# 04_ETHERNET.net
KiCad netlist of a schematic drawn in Altium Designer
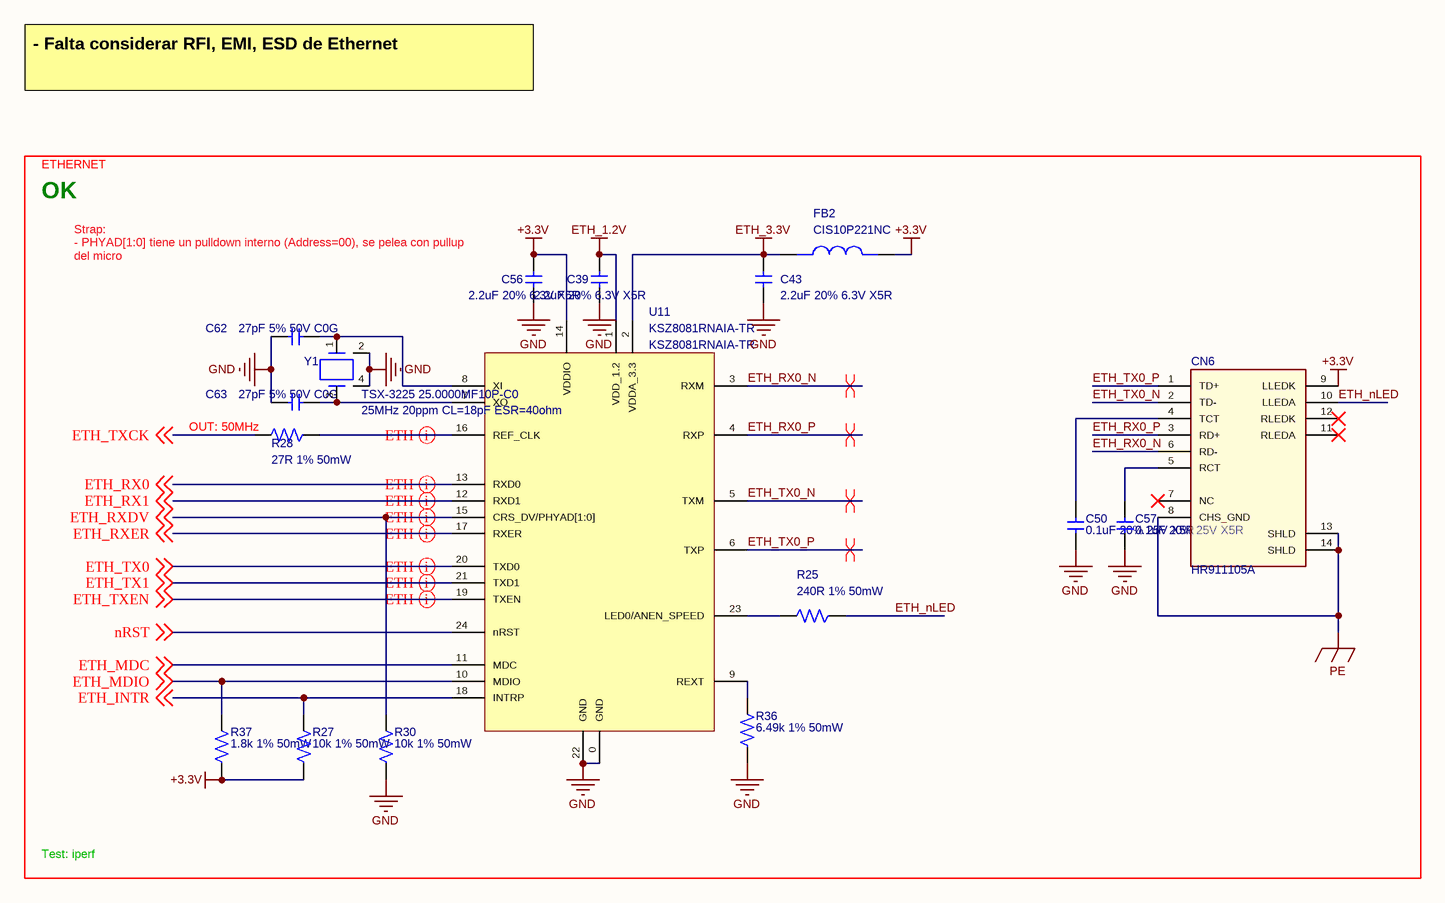
[diagram p0: 04_ETHERNET.SchDoc]

(export (version "E")
  (design (tool "Eeschema 10.0.6"))
  (components
    (comp (ref "C39")
      (value "2.2uF 20% 6.3V X5R")
      (footprint "CAPC1608X90N")
      (description "Capacitor, Ceramic")
      (fields
        (field (name "MFG") "SAMSUNG")
        (field (name "TOLERANCE") "20%")
        (field (name "FOOTPRINT CHECKED") "Assign OK, Footprint OK")
      )
      (libsource (lib "*") (part "C_Dup1"))
    )
    (comp (ref "C43")
      (value "2.2uF 20% 6.3V X5R")
      (footprint "CAPC1608X90N")
      (description "Capacitor, Ceramic")
      (fields
        (field (name "MFG") "SAMSUNG")
        (field (name "TOLERANCE") "20%")
        (field (name "FOOTPRINT CHECKED") "Assign OK, Footprint OK")
      )
      (libsource (lib "*") (part "C_Dup1"))
    )
    (comp (ref "C50")
      (value "0.1uF 20% 25V X5R")
      (footprint "CAPC1005N")
      (description "Capacitor, Ceramic")
      (fields
        (field (name "MFG") "SAMSUNG")
        (field (name "TOLERANCE") "20%")
        (field (name "FOOTPRINT CHECKED") "Assign OK, Footprint OK")
      )
      (libsource (lib "*") (part "C_Dup1"))
    )
    (comp (ref "C56")
      (value "2.2uF 20% 6.3V X5R")
      (footprint "CAPC1608X90N")
      (description "Capacitor, Ceramic")
      (fields
        (field (name "MFG") "SAMSUNG")
        (field (name "TOLERANCE") "20%")
        (field (name "FOOTPRINT CHECKED") "Assign OK, Footprint OK")
      )
      (libsource (lib "*") (part "C_Dup1"))
    )
    (comp (ref "C57")
      (value "0.1uF 20% 25V X5R")
      (footprint "CAPC1005N")
      (description "Capacitor, Ceramic")
      (fields
        (field (name "MFG") "SAMSUNG")
        (field (name "TOLERANCE") "20%")
        (field (name "FOOTPRINT CHECKED") "Assign OK, Footprint OK")
      )
      (libsource (lib "*") (part "C_Dup1"))
    )
    (comp (ref "C62")
      (value "27pF 5% 50V C0G")
      (footprint "CAPC1005N")
      (description "Capacitor, Ceramic")
      (fields
        (field (name "MFG") "<GENERIC>")
        (field (name "TOLERANCE") "5%")
        (field (name "FOOTPRINT CHECKED") "Assign OK, Footprint OK")
      )
      (libsource (lib "*") (part "C_Dup1"))
    )
    (comp (ref "C63")
      (value "27pF 5% 50V C0G")
      (footprint "CAPC1005N")
      (description "Capacitor, Ceramic")
      (fields
        (field (name "MFG") "<GENERIC>")
        (field (name "TOLERANCE") "5%")
        (field (name "FOOTPRINT CHECKED") "Assign OK, Footprint OK")
      )
      (libsource (lib "*") (part "C_Dup1"))
    )
    (comp (ref "CN6")
      (value "HR911105A")
      (footprint "HR911105A")
      (description "Single Port RJ45 connecto with Magnetics Module and LEDs")
      (fields (field (name "MFG") "HANRUN") (field (name "FOOTPRINT CHECKED") "Assign OK, Footprint OK"))
      (libsource (lib "sch") (part "HR911105A"))
    )
    (comp (ref "FB2")
      (value "CIS10P221NC")
      (footprint "INDC1608X95N")
      (description "Ferrite Bead")
      (fields (field (name "MFG") "SAMSUNG") (field (name "FOOTPRINT CHECKED") "Assign OK, Footprint OK"))
      (libsource (lib "*") (part "Filtre ferrites CMS-742792093"))
    )
    (comp (ref "R25")
      (value "240R 1% 50mW")
      (footprint "RESC1005X40N")
      (description "Resistor, SMD")
      (fields
        (field (name "MFG") "<GENERIC>")
        (field (name "POWER") "50mW")
        (field (name "FOOTPRINT CHECKED") "Assign OK, Footprint OK")
      )
      (libsource (lib "*") (part "R_Dup1"))
    )
    (comp (ref "R27")
      (value "10k 1% 50mW")
      (footprint "RESC1005X40N")
      (description "Resistor, SMD")
      (fields
        (field (name "MFG") "<GENERIC>")
        (field (name "POWER") "50mW")
        (field (name "FOOTPRINT CHECKED") "Assign OK, Footprint OK")
      )
      (libsource (lib "*") (part "R_Dup1"))
    )
    (comp (ref "R28")
      (value "27R 1% 50mW")
      (footprint "RESC1005X40N")
      (description "Resistor, SMD")
      (fields
        (field (name "MFG") "<GENERIC>")
        (field (name "POWER") "50mW")
        (field (name "FOOTPRINT CHECKED") "Assign OK, Footprint OK")
      )
      (libsource (lib "*") (part "R_Dup1"))
    )
    (comp (ref "R30")
      (value "10k 1% 50mW")
      (footprint "RESC1005X40N")
      (description "Resistor, SMD")
      (fields
        (field (name "MFG") "<GENERIC>")
        (field (name "POWER") "50mW")
        (field (name "FOOTPRINT CHECKED") "Assign OK, Footprint OK")
      )
      (libsource (lib "*") (part "R_Dup1"))
    )
    (comp (ref "R36")
      (value "6.49k 1% 50mW")
      (footprint "RESC1005X40N")
      (description "Resistor, SMD")
      (fields
        (field (name "MFG") "<GENERIC>")
        (field (name "POWER") "50mW")
        (field (name "FOOTPRINT CHECKED") "Assign OK, Footprint OK")
      )
      (libsource (lib "*") (part "R_Dup1"))
    )
    (comp (ref "R37")
      (value "1.8k 1% 50mW")
      (footprint "RESC1005X40N")
      (description "Resistor, SMD")
      (fields
        (field (name "MFG") "<GENERIC>")
        (field (name "POWER") "50mW")
        (field (name "FOOTPRINT CHECKED") "Assign OK, Footprint OK")
      )
      (libsource (lib "*") (part "R"))
    )
    (comp (ref "U11")
      (value "KSZ8081RNAIA-TR")
      (footprint "QFN50P400X400X80-25N")
      (description "10Base-T/100Base-TX PHY with RMII Support")
      (fields
        (field (name "MFG") "MICROCHIP")
        (field (name "MFG_PN") "KSZ8081RNAIA-TR")
        (field (name "FOOTPRINT CHECKED") "Assign OK, Footprint OK")
      )
      (libsource (lib "xct") (part "KSZ8081"))
    )
    (comp (ref "Y1")
      (value "TSX-3225 25.0000MF10P-C0")
      (footprint "SensorWireless:XTAL3.2x2.5")
      (description "Crystal")
      (fields
        (field (name "MFG") "EPSON")
        (field (name "ALTIUM_VALUE") "25MHz 20ppm CL=18pF ESR=40ohm")
        (field (name "FOOTPRINT CHECKED") "Assign OK, Footprint OK")
      )
      (libsource (lib "sch") (part "CS10-12MHz"))
    )
  )
  (nets
    (net (code "1") (name "+3.3V") (class "Default")
      (node (ref "C56") (pin "2") (pinfunction "2_2") (pintype "passive"))
      (node (ref "CN6") (pin "9") (pinfunction "LLEDK_9") (pintype "passive"))
      (node (ref "FB2") (pin "1") (pinfunction "1_1") (pintype "passive"))
      (node (ref "R27") (pin "1") (pinfunction "1_1") (pintype "passive"))
      (node (ref "R37") (pin "1") (pinfunction "1_1") (pintype "passive"))
      (node (ref "U11") (pin "14") (pinfunction "VDDIO_14") (pintype "passive"))
    )
    (net (code "2") (name "/ETH_RX0_N") (class "Default")
      (node (ref "CN6") (pin "6") (pinfunction "RD-_6") (pintype "passive"))
      (node (ref "U11") (pin "3") (pinfunction "RXM_3") (pintype "passive"))
    )
    (net (code "3") (name "/ETH_RX0_P") (class "Default")
      (node (ref "CN6") (pin "3") (pinfunction "RD+_3") (pintype "passive"))
      (node (ref "U11") (pin "4") (pinfunction "RXP_4") (pintype "passive"))
    )
    (net (code "4") (name "/ETH_TX0_N") (class "Default")
      (node (ref "CN6") (pin "2") (pinfunction "TD-_2") (pintype "passive"))
      (node (ref "U11") (pin "5") (pinfunction "TXM_5") (pintype "passive"))
    )
    (net (code "5") (name "/ETH_TX0_P") (class "Default")
      (node (ref "CN6") (pin "1") (pinfunction "TD+_1") (pintype "passive"))
      (node (ref "U11") (pin "6") (pinfunction "TXP_6") (pintype "passive"))
    )
    (net (code "6") (name "/ETH_nLED") (class "Default")
      (node (ref "CN6") (pin "10") (pinfunction "LLEDA_10") (pintype "passive"))
      (node (ref "R25") (pin "1") (pinfunction "1_1") (pintype "passive"))
    )
    (net (code "7") (name "ETH_1.2V") (class "Default")
      (node (ref "C39") (pin "2") (pinfunction "2_2") (pintype "passive"))
      (node (ref "U11") (pin "1") (pinfunction "VDD_1.2_1") (pintype "passive"))
    )
    (net (code "8") (name "ETH_3.3V") (class "Default")
      (node (ref "C43") (pin "2") (pinfunction "2_2") (pintype "passive"))
      (node (ref "FB2") (pin "2") (pinfunction "2_2") (pintype "passive"))
      (node (ref "U11") (pin "2") (pinfunction "VDDA_3.3_2") (pintype "passive"))
    )
    (net (code "9") (name "ETH_INTR") (class "Default")
      (node (ref "R27") (pin "2") (pinfunction "2_2") (pintype "passive"))
      (node (ref "U11") (pin "18") (pinfunction "INTRP_18") (pintype "passive"))
    )
    (net (code "10") (name "ETH_MDC") (class "Default")
      (node (ref "U11") (pin "11") (pinfunction "MDC_11") (pintype "passive"))
    )
    (net (code "11") (name "ETH_MDIO") (class "Default")
      (node (ref "R37") (pin "2") (pinfunction "2_2") (pintype "passive"))
      (node (ref "U11") (pin "10") (pinfunction "MDIO_10") (pintype "passive"))
    )
    (net (code "12") (name "ETH_RX0") (class "Default")
      (node (ref "U11") (pin "13") (pinfunction "RXD0_13") (pintype "passive"))
    )
    (net (code "13") (name "ETH_RX1") (class "Default")
      (node (ref "U11") (pin "12") (pinfunction "RXD1_12") (pintype "passive"))
    )
    (net (code "14") (name "ETH_RXDV") (class "Default")
      (node (ref "R30") (pin "2") (pinfunction "2_2") (pintype "passive"))
      (node (ref "U11") (pin "15") (pinfunction "CRS_DV/PHYAD[1:0]_15") (pintype "passive"))
    )
    (net (code "15") (name "ETH_RXER") (class "Default")
      (node (ref "U11") (pin "17") (pinfunction "RXER_17") (pintype "passive"))
    )
    (net (code "16") (name "ETH_TX0") (class "Default")
      (node (ref "U11") (pin "20") (pinfunction "TXD0_20") (pintype "passive"))
    )
    (net (code "17") (name "ETH_TX1") (class "Default")
      (node (ref "U11") (pin "21") (pinfunction "TXD1_21") (pintype "passive"))
    )
    (net (code "18") (name "ETH_TXCK") (class "Default")
      (node (ref "R28") (pin "2") (pinfunction "2_2") (pintype "passive"))
    )
    (net (code "19") (name "ETH_TXEN") (class "Default")
      (node (ref "U11") (pin "19") (pinfunction "TXEN_19") (pintype "passive"))
    )
    (net (code "20") (name "GND") (class "Default")
      (node (ref "C39") (pin "1") (pinfunction "1_1") (pintype "passive"))
      (node (ref "C43") (pin "1") (pinfunction "1_1") (pintype "passive"))
      (node (ref "C50") (pin "1") (pinfunction "1_1") (pintype "passive"))
      (node (ref "C56") (pin "1") (pinfunction "1_1") (pintype "passive"))
      (node (ref "C57") (pin "1") (pinfunction "1_1") (pintype "passive"))
      (node (ref "C62") (pin "1") (pinfunction "1_1") (pintype "passive"))
      (node (ref "C63") (pin "1") (pinfunction "1_1") (pintype "passive"))
      (node (ref "R30") (pin "1") (pinfunction "1_1") (pintype "passive"))
      (node (ref "R36") (pin "1") (pinfunction "1_1") (pintype "passive"))
      (node (ref "U11") (pin "0") (pinfunction "GND_0") (pintype "passive"))
      (node (ref "U11") (pin "22") (pinfunction "GND_22") (pintype "passive"))
      (node (ref "Y1") (pin "2") (pinfunction "GND_2") (pintype "passive"))
      (node (ref "Y1") (pin "4") (pinfunction "GND_4") (pintype "passive"))
    )
    (net (code "21") (name "Net-(CN6-RCT)") (class "Default")
      (node (ref "C57") (pin "2") (pinfunction "2_2") (pintype "passive"))
      (node (ref "CN6") (pin "5") (pinfunction "RCT_5") (pintype "passive"))
    )
    (net (code "22") (name "Net-(CN6-TCT)") (class "Default")
      (node (ref "C50") (pin "2") (pinfunction "2_2") (pintype "passive"))
      (node (ref "CN6") (pin "4") (pinfunction "TCT_4") (pintype "passive"))
    )
    (net (code "23") (name "Net-(U11-LED0{slash}ANEN_SPEED)") (class "Default")
      (node (ref "R25") (pin "2") (pinfunction "2_2") (pintype "passive"))
      (node (ref "U11") (pin "23") (pinfunction "LED0/ANEN_SPEED_23") (pintype "passive"))
    )
    (net (code "24") (name "Net-(U11-REF_CLK)") (class "Default")
      (node (ref "R28") (pin "1") (pinfunction "1_1") (pintype "passive"))
      (node (ref "U11") (pin "16") (pinfunction "REF_CLK_16") (pintype "passive"))
    )
    (net (code "25") (name "Net-(U11-REXT)") (class "Default")
      (node (ref "R36") (pin "2") (pinfunction "2_2") (pintype "passive"))
      (node (ref "U11") (pin "9") (pinfunction "REXT_9") (pintype "passive"))
    )
    (net (code "26") (name "Net-(U11-XI)") (class "Default")
      (node (ref "C62") (pin "2") (pinfunction "2_2") (pintype "passive"))
      (node (ref "U11") (pin "8") (pinfunction "XI_8") (pintype "passive"))
      (node (ref "Y1") (pin "1") (pinfunction "S1_1") (pintype "passive"))
    )
    (net (code "27") (name "Net-(U11-XO)") (class "Default")
      (node (ref "C63") (pin "2") (pinfunction "2_2") (pintype "passive"))
      (node (ref "U11") (pin "7") (pinfunction "XO_7") (pintype "passive"))
      (node (ref "Y1") (pin "3") (pinfunction "S2_3") (pintype "passive"))
    )
    (net (code "28") (name "PE") (class "Default")
      (node (ref "CN6") (pin "13") (pinfunction "SHLD_13") (pintype "passive"))
      (node (ref "CN6") (pin "14") (pinfunction "SHLD_14") (pintype "passive"))
      (node (ref "CN6") (pin "8") (pinfunction "CHS_GND_8") (pintype "passive"))
    )
    (net (code "29") (name "nRST") (class "Default")
      (node (ref "U11") (pin "24") (pinfunction "nRST_24") (pintype "passive"))
    )
    (net (code "30") (name "unconnected-(CN6-NC-Pad7)") (class "Default")
      (node (ref "CN6") (pin "7") (pinfunction "NC_7") (pintype "passive+no_connect"))
    )
    (net (code "31") (name "unconnected-(CN6-RLEDA-Pad11)") (class "Default")
      (node (ref "CN6") (pin "11") (pinfunction "RLEDA_11") (pintype "passive+no_connect"))
    )
    (net (code "32") (name "unconnected-(CN6-RLEDK-Pad12)") (class "Default")
      (node (ref "CN6") (pin "12") (pinfunction "RLEDK_12") (pintype "passive+no_connect"))
    )
  )
)
